# Feuchte-Relais-mit-LCD_v2.net
KiCad netlist of a schematic drawn in EAGLE
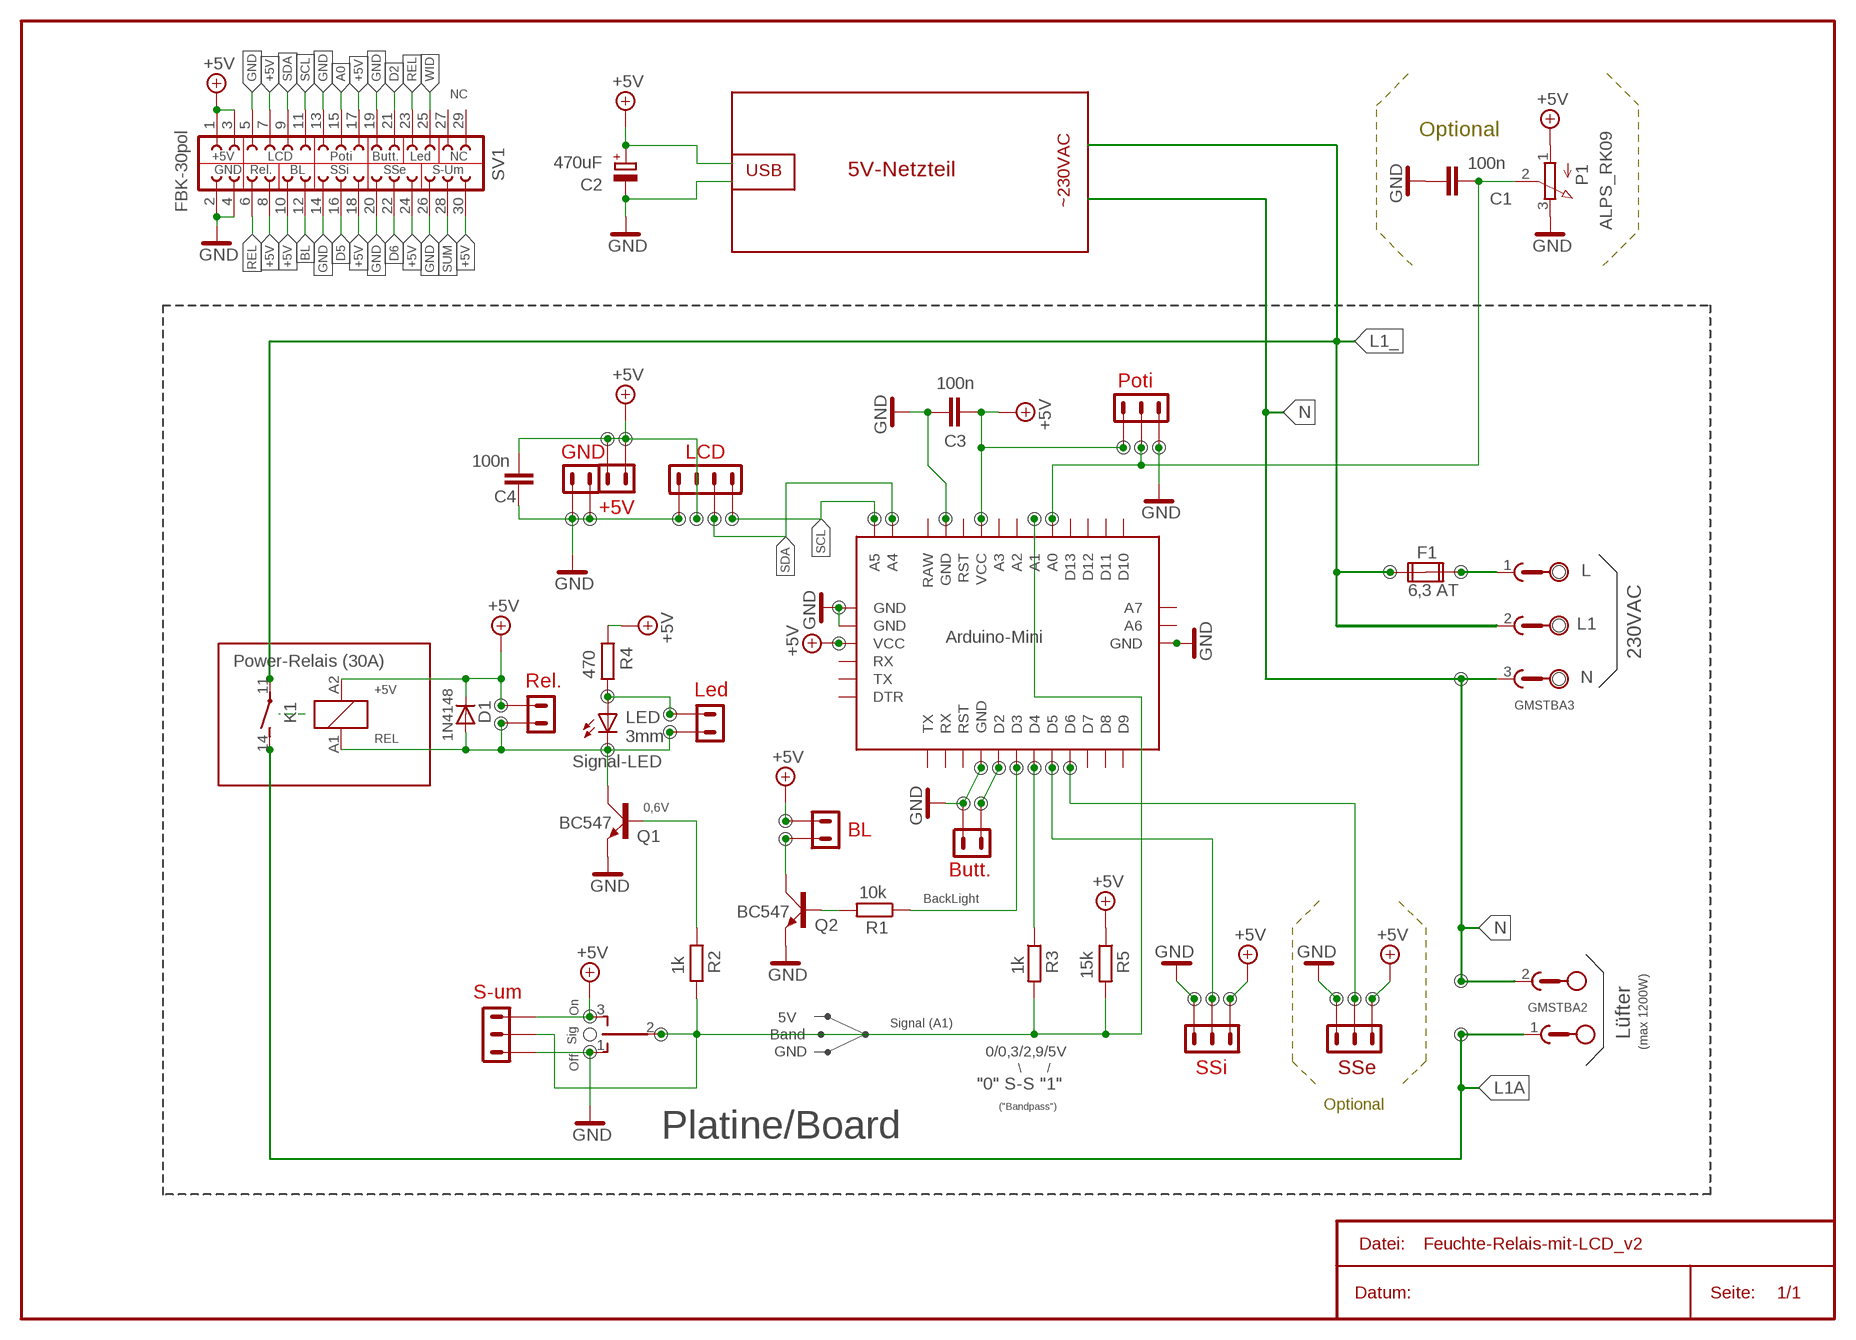
[diagram p0: schematic, sheet 1]

(export (version "E")
  (design (tool "Eeschema 10.0.6"))
  (components
    (comp (ref "230VAC")
      (value "GMSTBA3")
      (footprint "eagle-import:GMSTBA3")
      (fields (field (name "MF") "FARNELL") (field (name "MPN") "1757255"))
      (libsource (lib "eagle-import") (part "GMSTBA3"))
    )
    (comp (ref "BOARD")
      (value "Arduino-Mini")
      (footprint "eagle-import:ARDU-MINI")
      (libsource (lib "eagle-import") (part "ARDU-MINI"))
    )
    (comp (ref "C1")
      (value "100n")
      (footprint "eagle-import:C025-024X044")
      (libsource (lib "eagle-import") (part "C-EU025-024X044"))
    )
    (comp (ref "C2")
      (value "470uF")
      (footprint "eagle-import:E3,5-8")
      (libsource (lib "eagle-import") (part "CPOL-EUE3.5-8"))
    )
    (comp (ref "C3")
      (value "100n")
      (footprint "eagle-import:C025-024X044")
      (libsource (lib "eagle-import") (part "C-EU025-024X044"))
    )
    (comp (ref "C4")
      (value "100n")
      (footprint "eagle-import:C025-024X044")
      (libsource (lib "eagle-import") (part "C-EU025-024X044"))
    )
    (comp (ref "D1")
      (value "1N4148")
      (footprint "eagle-import:D-2.5")
      (libsource (lib "eagle-import") (part "DIODE-D-2.5"))
    )
    (comp (ref "F1")
      (value "6,3 AT")
      (footprint "eagle-import:FUSE1")
      (libsource (lib "eagle-import") (part "FUSE2P"))
    )
    (comp (ref "K1")
      (value "Power-Relais (30A)")
      (footprint "eagle-import:ZD2")
      (libsource (lib "eagle-import") (part "ZD?232006"))
    )
    (comp (ref "LED1")
      (value "o3mm")
      (footprint "eagle-import:LED3MM")
      (libsource (lib "eagle-import") (part "LED3MM"))
    )
    (comp (ref "LüFTER")
      (value "GMSTBA2")
      (footprint "eagle-import:GMSTBA2")
      (fields (field (name "MF") "FARNELL") (field (name "MPN") "1757242"))
      (libsource (lib "eagle-import") (part "GMSTBA2"))
    )
    (comp (ref "P1")
      (value "ALPS_RK09")
      (footprint "eagle-import:RK09")
      (libsource (lib "eagle-import") (part "ALPS_RK09"))
    )
    (comp (ref "Q1")
      (value "BC547")
      (footprint "eagle-import:SOT54A")
      (libsource (lib "eagle-import") (part "BC547"))
    )
    (comp (ref "Q2")
      (value "BC547")
      (footprint "eagle-import:SOT54A")
      (libsource (lib "eagle-import") (part "BC547"))
    )
    (comp (ref "R1")
      (value "10k")
      (footprint "eagle-import:0204_7")
      (libsource (lib "eagle-import") (part "R-EU_0204/7"))
    )
    (comp (ref "R2")
      (value "1k")
      (footprint "eagle-import:0204V")
      (libsource (lib "eagle-import") (part "R-EU_0204/2V"))
    )
    (comp (ref "R3")
      (value "1k")
      (footprint "eagle-import:0204V")
      (libsource (lib "eagle-import") (part "R-EU_0204/2V"))
    )
    (comp (ref "R4")
      (value "470")
      (footprint "eagle-import:0204V")
      (libsource (lib "eagle-import") (part "R-EU_0204/2V"))
    )
    (comp (ref "R5")
      (value "15k")
      (footprint "eagle-import:0204V")
      (libsource (lib "eagle-import") (part "R-EU_0204/2V"))
    )
    (comp (ref "SUM")
      (value "TL39PO")
      (footprint "eagle-import:TL3XPO")
      (libsource (lib "eagle-import") (part "TL39PO"))
    )
    (comp (ref "SV1")
      (value "FBK-30pol")
      (footprint "eagle-import:FE15-2")
      (libsource (lib "eagle-import") (part "FE15-2"))
    )
  )
  (nets
    (net (code "1") (name "+5V") (class "Default")
      (node (ref "BOARD") (pin "P$21") (pinfunction "VCC_P$21") (pintype "input"))
      (node (ref "BOARD") (pin "P$27") (pinfunction "VCC_P$27") (pintype "input"))
      (node (ref "C2") (pin "+") (pinfunction "+_+") (pintype "passive"))
      (node (ref "C3") (pin "1") (pinfunction "1_1") (pintype "passive"))
      (node (ref "C4") (pin "2") (pinfunction "2_2") (pintype "passive"))
      (node (ref "D1") (pin "C") (pinfunction "C_C") (pintype "passive"))
      (node (ref "K1") (pin "A2") (pinfunction "2_A2") (pintype "passive"))
      (node (ref "P1") (pin "1") (pinfunction "A_1") (pintype "passive"))
      (node (ref "R4") (pin "1") (pinfunction "1_1") (pintype "passive"))
      (node (ref "R5") (pin "1") (pinfunction "1_1") (pintype "passive"))
      (node (ref "SUM") (pin "3") (pinfunction "S_3") (pintype "passive"))
      (node (ref "SV1") (pin "1") (pinfunction "1_1") (pintype "passive"))
      (node (ref "SV1") (pin "10") (pinfunction "10_10") (pintype "passive"))
      (node (ref "SV1") (pin "17") (pinfunction "17_17") (pintype "passive"))
      (node (ref "SV1") (pin "18") (pinfunction "18_18") (pintype "passive"))
      (node (ref "SV1") (pin "24") (pinfunction "24_24") (pintype "passive"))
      (node (ref "SV1") (pin "3") (pinfunction "3_3") (pintype "passive"))
      (node (ref "SV1") (pin "30") (pinfunction "30_30") (pintype "passive"))
      (node (ref "SV1") (pin "7") (pinfunction "7_7") (pintype "passive"))
      (node (ref "SV1") (pin "8") (pinfunction "8_8") (pintype "passive"))
    )
    (net (code "2") (name "A0") (class "Default")
      (node (ref "BOARD") (pin "P$17") (pinfunction "A0_P$17") (pintype "bidirectional"))
      (node (ref "C1") (pin "2") (pinfunction "2_2") (pintype "passive"))
      (node (ref "P1") (pin "2") (pinfunction "S_2") (pintype "passive"))
      (node (ref "SV1") (pin "15") (pinfunction "15_15") (pintype "passive"))
    )
    (net (code "3") (name "BL") (class "Default")
      (node (ref "Q2") (pin "C") (pinfunction "C_C") (pintype "passive"))
      (node (ref "SV1") (pin "12") (pinfunction "12_12") (pintype "passive"))
    )
    (net (code "4") (name "D2") (class "Default")
      (node (ref "BOARD") (pin "P$5") (pinfunction "D2_P$5") (pintype "bidirectional"))
      (node (ref "SV1") (pin "21") (pinfunction "21_21") (pintype "passive"))
    )
    (net (code "5") (name "D5") (class "Default")
      (node (ref "BOARD") (pin "P$8") (pinfunction "D5_P$8") (pintype "bidirectional"))
      (node (ref "SV1") (pin "16") (pinfunction "16_16") (pintype "passive"))
    )
    (net (code "6") (name "D6") (class "Default")
      (node (ref "BOARD") (pin "P$9") (pinfunction "D6_P$9") (pintype "bidirectional"))
      (node (ref "SV1") (pin "22") (pinfunction "22_22") (pintype "passive"))
    )
    (net (code "7") (name "GND") (class "Default")
      (node (ref "BOARD") (pin "P$23") (pinfunction "GND_P$23") (pintype "input"))
      (node (ref "BOARD") (pin "P$25") (pinfunction "GND_P$25") (pintype "input"))
      (node (ref "BOARD") (pin "P$26") (pinfunction "GND_P$26") (pintype "input"))
      (node (ref "BOARD") (pin "P$31") (pinfunction "GND_P$31") (pintype "input"))
      (node (ref "BOARD") (pin "P$4") (pinfunction "GND_P$4") (pintype "input"))
      (node (ref "C1") (pin "1") (pinfunction "1_1") (pintype "passive"))
      (node (ref "C2") (pin "-") (pinfunction "-_-") (pintype "passive"))
      (node (ref "C3") (pin "2") (pinfunction "2_2") (pintype "passive"))
      (node (ref "C4") (pin "1") (pinfunction "1_1") (pintype "passive"))
      (node (ref "P1") (pin "3") (pinfunction "E_3") (pintype "passive"))
      (node (ref "Q1") (pin "E") (pinfunction "E_E") (pintype "passive"))
      (node (ref "Q2") (pin "E") (pinfunction "E_E") (pintype "passive"))
      (node (ref "SUM") (pin "1") (pinfunction "O_1") (pintype "passive"))
      (node (ref "SV1") (pin "13") (pinfunction "13_13") (pintype "passive"))
      (node (ref "SV1") (pin "14") (pinfunction "14_14") (pintype "passive"))
      (node (ref "SV1") (pin "19") (pinfunction "19_19") (pintype "passive"))
      (node (ref "SV1") (pin "2") (pinfunction "2_2") (pintype "passive"))
      (node (ref "SV1") (pin "20") (pinfunction "20_20") (pintype "passive"))
      (node (ref "SV1") (pin "26") (pinfunction "26_26") (pintype "passive"))
      (node (ref "SV1") (pin "4") (pinfunction "4_4") (pintype "passive"))
      (node (ref "SV1") (pin "5") (pinfunction "5_5") (pintype "passive"))
    )
    (net (code "8") (name "L1A") (class "Default")
      (node (ref "K1") (pin "14") (pinfunction "S_14") (pintype "passive"))
      (node (ref "LüFTER") (pin "1") (pinfunction "1_1") (pintype "passive"))
    )
    (net (code "9") (name "L1_") (class "Default")
      (node (ref "230VAC") (pin "2") (pinfunction "1_2") (pintype "passive"))
      (node (ref "F1") (pin "1A") (pinfunction "1A_1A") (pintype "passive"))
      (node (ref "K1") (pin "11") (pinfunction "P_11") (pintype "passive"))
    )
    (net (code "10") (name "N") (class "Default")
      (node (ref "230VAC") (pin "3") (pinfunction "1_3") (pintype "passive"))
      (node (ref "LüFTER") (pin "2") (pinfunction "1_2") (pintype "passive"))
    )
    (net (code "11") (name "Net-(230VAC-Pad1)") (class "Default")
      (node (ref "230VAC") (pin "1") (pinfunction "1_1") (pintype "passive"))
      (node (ref "F1") (pin "2A") (pinfunction "2A_2A") (pintype "passive"))
    )
    (net (code "12") (name "Net-(BOARD-A1)") (class "Default")
      (node (ref "BOARD") (pin "P$18") (pinfunction "A1_P$18") (pintype "bidirectional"))
      (node (ref "R2") (pin "1") (pinfunction "1_1") (pintype "passive"))
      (node (ref "R3") (pin "2") (pinfunction "2_2") (pintype "passive"))
      (node (ref "R5") (pin "2") (pinfunction "2_2") (pintype "passive"))
      (node (ref "SUM") (pin "2") (pinfunction "P_2") (pintype "passive"))
    )
    (net (code "13") (name "Net-(BOARD-D3)") (class "Default")
      (node (ref "BOARD") (pin "P$6") (pinfunction "D3_P$6") (pintype "bidirectional"))
      (node (ref "R1") (pin "1") (pinfunction "1_1") (pintype "passive"))
    )
    (net (code "14") (name "Net-(BOARD-D4)") (class "Default")
      (node (ref "BOARD") (pin "P$7") (pinfunction "D4_P$7") (pintype "bidirectional"))
      (node (ref "R3") (pin "1") (pinfunction "1_1") (pintype "passive"))
    )
    (net (code "15") (name "Net-(Q1-PadB)") (class "Default")
      (node (ref "Q1") (pin "B") (pinfunction "B_B") (pintype "passive"))
      (node (ref "R2") (pin "2") (pinfunction "2_2") (pintype "passive"))
    )
    (net (code "16") (name "Net-(Q2-PadB)") (class "Default")
      (node (ref "Q2") (pin "B") (pinfunction "B_B") (pintype "passive"))
      (node (ref "R1") (pin "2") (pinfunction "2_2") (pintype "passive"))
    )
    (net (code "17") (name "REL") (class "Default")
      (node (ref "D1") (pin "A") (pinfunction "A_A") (pintype "passive"))
      (node (ref "K1") (pin "A1") (pinfunction "1_A1") (pintype "passive"))
      (node (ref "LED1") (pin "K") (pinfunction "C_K") (pintype "passive"))
      (node (ref "Q1") (pin "C") (pinfunction "C_C") (pintype "passive"))
      (node (ref "SV1") (pin "23") (pinfunction "23_23") (pintype "passive"))
      (node (ref "SV1") (pin "6") (pinfunction "6_6") (pintype "passive"))
    )
    (net (code "18") (name "SCL") (class "Default")
      (node (ref "BOARD") (pin "P$35") (pinfunction "A5_P$35") (pintype "bidirectional"))
      (node (ref "SV1") (pin "11") (pinfunction "11_11") (pintype "passive"))
    )
    (net (code "19") (name "SDA") (class "Default")
      (node (ref "BOARD") (pin "P$34") (pinfunction "A4_P$34") (pintype "bidirectional"))
      (node (ref "SV1") (pin "9") (pinfunction "9_9") (pintype "passive"))
    )
    (net (code "20") (name "SUM") (class "Default")
      (node (ref "SV1") (pin "28") (pinfunction "28_28") (pintype "passive"))
    )
    (net (code "21") (name "WID") (class "Default")
      (node (ref "LED1") (pin "A") (pinfunction "A_A") (pintype "passive"))
      (node (ref "R4") (pin "2") (pinfunction "2_2") (pintype "passive"))
      (node (ref "SV1") (pin "25") (pinfunction "25_25") (pintype "passive"))
    )
    (net (code "22") (name "unconnected-(BOARD-A2-PadP$19)") (class "Default")
      (node (ref "BOARD") (pin "P$19") (pinfunction "A2_P$19") (pintype "bidirectional"))
    )
    (net (code "23") (name "unconnected-(BOARD-A3-PadP$20)") (class "Default")
      (node (ref "BOARD") (pin "P$20") (pinfunction "A3_P$20") (pintype "bidirectional"))
    )
    (net (code "24") (name "unconnected-(BOARD-A6-PadP$32)") (class "Default")
      (node (ref "BOARD") (pin "P$32") (pinfunction "A6_P$32") (pintype "bidirectional"))
    )
    (net (code "25") (name "unconnected-(BOARD-A7-PadP$33)") (class "Default")
      (node (ref "BOARD") (pin "P$33") (pinfunction "A7_P$33") (pintype "bidirectional"))
    )
    (net (code "26") (name "unconnected-(BOARD-D7-PadP$10)") (class "Default")
      (node (ref "BOARD") (pin "P$10") (pinfunction "D7_P$10") (pintype "bidirectional"))
    )
    (net (code "27") (name "unconnected-(BOARD-D8-PadP$11)") (class "Default")
      (node (ref "BOARD") (pin "P$11") (pinfunction "D8_P$11") (pintype "bidirectional"))
    )
    (net (code "28") (name "unconnected-(BOARD-D9-PadP$12)") (class "Default")
      (node (ref "BOARD") (pin "P$12") (pinfunction "D9_P$12") (pintype "bidirectional"))
    )
    (net (code "29") (name "unconnected-(BOARD-D10-PadP$13)") (class "Default")
      (node (ref "BOARD") (pin "P$13") (pinfunction "D10_P$13") (pintype "bidirectional"))
    )
    (net (code "30") (name "unconnected-(BOARD-D11-PadP$14)") (class "Default")
      (node (ref "BOARD") (pin "P$14") (pinfunction "D11_P$14") (pintype "bidirectional"))
    )
    (net (code "31") (name "unconnected-(BOARD-D12-PadP$15)") (class "Default")
      (node (ref "BOARD") (pin "P$15") (pinfunction "D12_P$15") (pintype "bidirectional"))
    )
    (net (code "32") (name "unconnected-(BOARD-D13-PadP$16)") (class "Default")
      (node (ref "BOARD") (pin "P$16") (pinfunction "D13_P$16") (pintype "bidirectional"))
    )
    (net (code "33") (name "unconnected-(BOARD-DTR-PadP$30)") (class "Default")
      (node (ref "BOARD") (pin "P$30") (pinfunction "DTR_P$30") (pintype "bidirectional"))
    )
    (net (code "34") (name "unconnected-(BOARD-RAW-PadP$24)") (class "Default")
      (node (ref "BOARD") (pin "P$24") (pinfunction "RAW_P$24") (pintype "input"))
    )
    (net (code "35") (name "unconnected-(BOARD-RST-PadP$3)") (class "Default")
      (node (ref "BOARD") (pin "P$3") (pinfunction "RST_P$3") (pintype "bidirectional"))
    )
    (net (code "36") (name "unconnected-(BOARD-RST-PadP$22)") (class "Default")
      (node (ref "BOARD") (pin "P$22") (pinfunction "RST_P$22") (pintype "bidirectional"))
    )
    (net (code "37") (name "unconnected-(BOARD-RX-PadP$2)") (class "Default")
      (node (ref "BOARD") (pin "P$2") (pinfunction "RX_P$2") (pintype "bidirectional"))
    )
    (net (code "38") (name "unconnected-(BOARD-RX-PadP$28)") (class "Default")
      (node (ref "BOARD") (pin "P$28") (pinfunction "RX_P$28") (pintype "bidirectional"))
    )
    (net (code "39") (name "unconnected-(BOARD-TX-PadP$1)") (class "Default")
      (node (ref "BOARD") (pin "P$1") (pinfunction "TX_P$1") (pintype "bidirectional"))
    )
    (net (code "40") (name "unconnected-(BOARD-TX-PadP$29)") (class "Default")
      (node (ref "BOARD") (pin "P$29") (pinfunction "TX_P$29") (pintype "bidirectional"))
    )
    (net (code "41") (name "unconnected-(F1-Pad1B)") (class "Default")
      (node (ref "F1") (pin "1B") (pinfunction "1B_1B") (pintype "passive"))
    )
    (net (code "42") (name "unconnected-(F1-Pad2B)") (class "Default")
      (node (ref "F1") (pin "2B") (pinfunction "2B_2B") (pintype "passive"))
    )
    (net (code "43") (name "unconnected-(SV1-Pad27)") (class "Default")
      (node (ref "SV1") (pin "27") (pinfunction "27_27") (pintype "passive"))
    )
    (net (code "44") (name "unconnected-(SV1-Pad29)") (class "Default")
      (node (ref "SV1") (pin "29") (pinfunction "29_29") (pintype "passive"))
    )
  )
)
